# BMS.net
KiCad netlist of a schematic drawn in Altium Designer
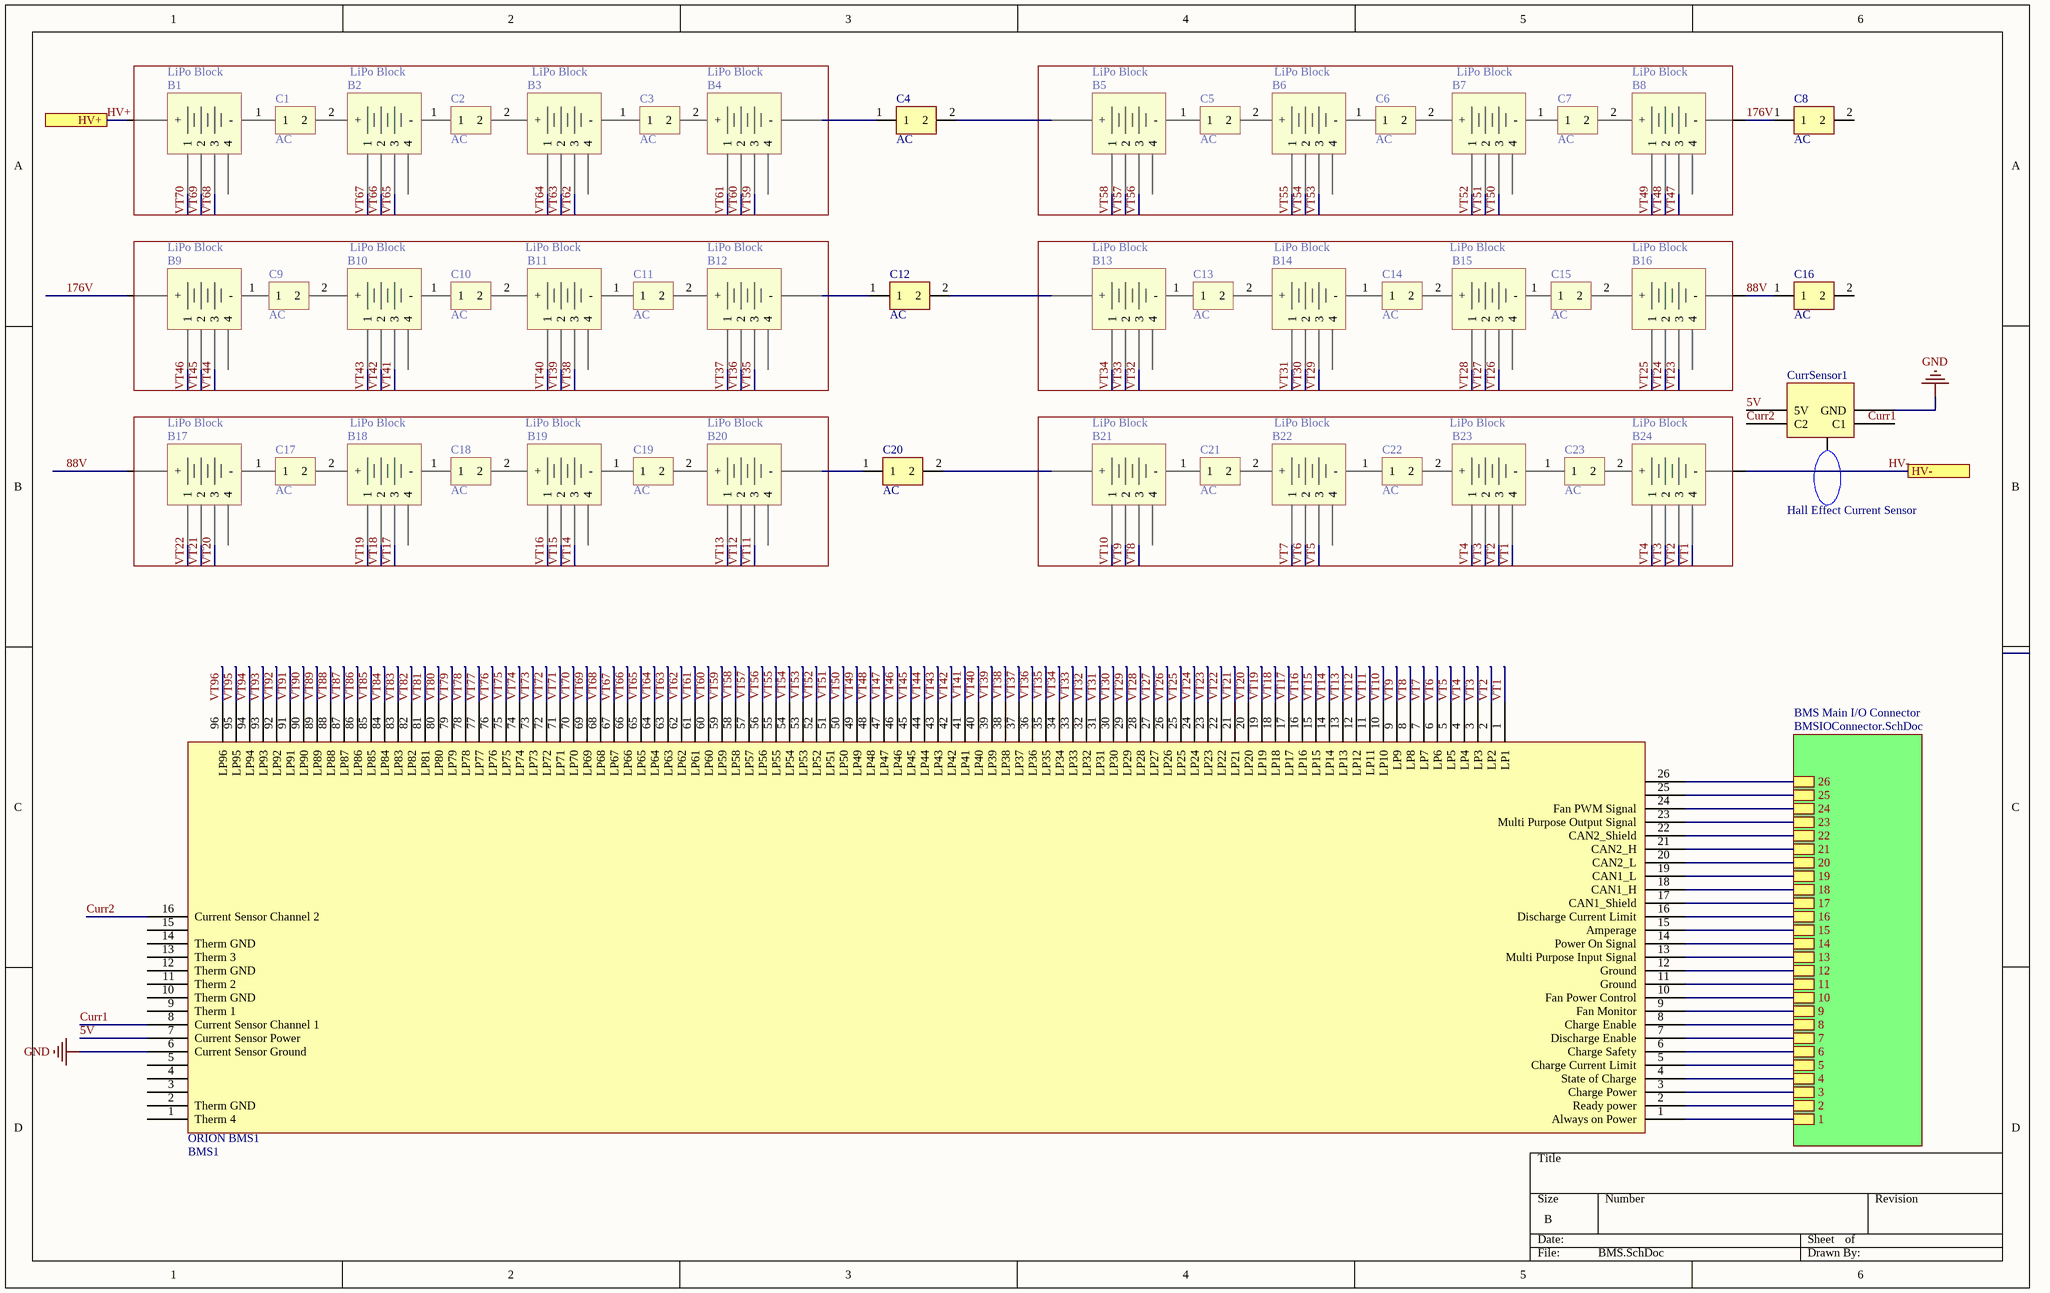
[diagram p0: BMS.SchDoc]

(export (version "E")
  (design (tool "Eeschema 10.0.6"))
  (components
    (comp (ref "B1") (value "LiPo Block") (libsource (lib "Pod3") (part "Li-Ion Cell")))
    (comp (ref "B2") (value "LiPo Block") (libsource (lib "Pod3") (part "Li-Ion Cell")))
    (comp (ref "B3") (value "LiPo Block") (libsource (lib "Pod3") (part "Li-Ion Cell")))
    (comp (ref "B4") (value "LiPo Block") (libsource (lib "Pod3") (part "Li-Ion Cell")))
    (comp (ref "B5") (value "LiPo Block") (libsource (lib "Pod3") (part "Li-Ion Cell")))
    (comp (ref "B6") (value "LiPo Block") (libsource (lib "Pod3") (part "Li-Ion Cell")))
    (comp (ref "B7") (value "LiPo Block") (libsource (lib "Pod3") (part "Li-Ion Cell")))
    (comp (ref "B8") (value "LiPo Block") (libsource (lib "Pod3") (part "Li-Ion Cell")))
    (comp (ref "B9") (value "LiPo Block") (libsource (lib "Pod3") (part "Li-Ion Cell")))
    (comp (ref "B10") (value "LiPo Block") (libsource (lib "Pod3") (part "Li-Ion Cell")))
    (comp (ref "B11") (value "LiPo Block") (libsource (lib "Pod3") (part "Li-Ion Cell")))
    (comp (ref "B12") (value "LiPo Block") (libsource (lib "Pod3") (part "Li-Ion Cell")))
    (comp (ref "B13") (value "LiPo Block") (libsource (lib "Pod3") (part "Li-Ion Cell")))
    (comp (ref "B14") (value "LiPo Block") (libsource (lib "Pod3") (part "Li-Ion Cell")))
    (comp (ref "B15") (value "LiPo Block") (libsource (lib "Pod3") (part "Li-Ion Cell")))
    (comp (ref "B16") (value "LiPo Block") (libsource (lib "Pod3") (part "Li-Ion Cell")))
    (comp (ref "B17") (value "LiPo Block") (libsource (lib "Pod3") (part "Li-Ion Cell")))
    (comp (ref "B18") (value "LiPo Block") (libsource (lib "Pod3") (part "Li-Ion Cell")))
    (comp (ref "B19") (value "LiPo Block") (libsource (lib "Pod3") (part "Li-Ion Cell")))
    (comp (ref "B20") (value "LiPo Block") (libsource (lib "Pod3") (part "Li-Ion Cell")))
    (comp (ref "B21") (value "LiPo Block") (libsource (lib "Pod3") (part "Li-Ion Cell")))
    (comp (ref "B22") (value "LiPo Block") (libsource (lib "Pod3") (part "Li-Ion Cell")))
    (comp (ref "B23") (value "LiPo Block") (libsource (lib "Pod3") (part "Li-Ion Cell")))
    (comp (ref "B24") (value "LiPo Block") (libsource (lib "Pod3") (part "Li-Ion Cell")))
    (comp (ref "C1") (value "AC") (libsource (lib "Pod3") (part "Anderson Connector")))
    (comp (ref "C2") (value "AC") (libsource (lib "Pod3") (part "Anderson Connector")))
    (comp (ref "C3") (value "AC") (libsource (lib "Pod3") (part "Anderson Connector")))
    (comp (ref "C4") (value "AC") (libsource (lib "Pod3") (part "Anderson Connector")))
    (comp (ref "C5") (value "AC") (libsource (lib "Pod3") (part "Anderson Connector")))
    (comp (ref "C6") (value "AC") (libsource (lib "Pod3") (part "Anderson Connector")))
    (comp (ref "C7") (value "AC") (libsource (lib "Pod3") (part "Anderson Connector")))
    (comp (ref "C8") (value "AC") (libsource (lib "Pod3") (part "Anderson Connector")))
    (comp (ref "C9") (value "AC") (libsource (lib "Pod3") (part "Anderson Connector")))
    (comp (ref "C10") (value "AC") (libsource (lib "Pod3") (part "Anderson Connector")))
    (comp (ref "C11") (value "AC") (libsource (lib "Pod3") (part "Anderson Connector")))
    (comp (ref "C12") (value "AC") (libsource (lib "Pod3") (part "Anderson Connector")))
    (comp (ref "C13") (value "AC") (libsource (lib "Pod3") (part "Anderson Connector")))
    (comp (ref "C14") (value "AC") (libsource (lib "Pod3") (part "Anderson Connector")))
    (comp (ref "C15") (value "AC") (libsource (lib "Pod3") (part "Anderson Connector")))
    (comp (ref "C16") (value "AC") (libsource (lib "Pod3") (part "Anderson Connector")))
    (comp (ref "C17") (value "AC") (libsource (lib "Pod3") (part "Anderson Connector")))
    (comp (ref "C18") (value "AC") (libsource (lib "Pod3") (part "Anderson Connector")))
    (comp (ref "C19") (value "AC") (libsource (lib "Pod3") (part "Anderson Connector")))
    (comp (ref "C20") (value "AC") (libsource (lib "Pod3") (part "Anderson Connector")))
    (comp (ref "C21") (value "AC") (libsource (lib "Pod3") (part "Anderson Connector")))
    (comp (ref "C22") (value "AC") (libsource (lib "Pod3") (part "Anderson Connector")))
    (comp (ref "C23") (value "AC") (libsource (lib "Pod3") (part "Anderson Connector")))
    (comp (ref "CurrSensor1")
      (value "Hall Effect Current Sensor")
      (libsource (lib "Pod3") (part "Hall Effect Current Sensor"))
    )
    (comp (ref "ORION BMS1") (value "BMS1") (libsource (lib "Pod3") (part "ORION BMS")))
  )
  (nets
    (net (code "1") (name "/1") (class "Default")
      (node (ref "ORION BMS1") (pin "1") (pinfunction "Always_on_Power_1") (pintype "passive"))
    )
    (net (code "2") (name "/2") (class "Default")
      (node (ref "ORION BMS1") (pin "2") (pinfunction "Ready_power_2") (pintype "passive"))
    )
    (net (code "3") (name "/3") (class "Default")
      (node (ref "ORION BMS1") (pin "3") (pinfunction "Charge_Power_3") (pintype "passive"))
    )
    (net (code "4") (name "/4") (class "Default")
      (node (ref "ORION BMS1") (pin "4") (pinfunction "State_of_Charge_4") (pintype "passive"))
    )
    (net (code "5") (name "/5") (class "Default")
      (node (ref "ORION BMS1") (pin "5") (pinfunction "Charge_Current_Limit_5") (pintype "passive"))
    )
    (net (code "6") (name "/5V") (class "Default")
      (node (ref "CurrSensor1") (pin "3") (pinfunction "5V_3") (pintype "passive"))
      (node (ref "ORION BMS1") (pin "7") (pinfunction "Current_Sensor_Power_7") (pintype "passive"))
    )
    (net (code "7") (name "/6") (class "Default")
      (node (ref "ORION BMS1") (pin "6") (pinfunction "Charge_Safety_6") (pintype "passive"))
    )
    (net (code "8") (name "/7") (class "Default")
      (node (ref "ORION BMS1") (pin "7") (pinfunction "Discharge_Enable_7") (pintype "passive"))
    )
    (net (code "9") (name "/8") (class "Default")
      (node (ref "ORION BMS1") (pin "8") (pinfunction "Charge_Enable_8") (pintype "passive"))
    )
    (net (code "10") (name "/9") (class "Default")
      (node (ref "ORION BMS1") (pin "9") (pinfunction "Fan_Monitor_9") (pintype "passive"))
    )
    (net (code "11") (name "/10") (class "Default")
      (node (ref "ORION BMS1") (pin "10") (pinfunction "Fan_Power_Control_10") (pintype "passive"))
    )
    (net (code "12") (name "/11") (class "Default")
      (node (ref "ORION BMS1") (pin "11") (pinfunction "Ground_11") (pintype "passive"))
    )
    (net (code "13") (name "/12") (class "Default")
      (node (ref "ORION BMS1") (pin "12") (pinfunction "Ground_12") (pintype "passive"))
    )
    (net (code "14") (name "/13") (class "Default")
      (node (ref "ORION BMS1") (pin "13") (pinfunction "Multi_Purpose_Input_Signal_13") (pintype "passive"))
    )
    (net (code "15") (name "/14") (class "Default")
      (node (ref "ORION BMS1") (pin "14") (pinfunction "Power_On_Signal_14") (pintype "passive"))
    )
    (net (code "16") (name "/15") (class "Default")
      (node (ref "ORION BMS1") (pin "15") (pinfunction "Amperage_15") (pintype "passive"))
    )
    (net (code "17") (name "/16") (class "Default")
      (node (ref "ORION BMS1") (pin "16") (pinfunction "Discharge_Current_Limit_16") (pintype "passive"))
    )
    (net (code "18") (name "/17") (class "Default")
      (node (ref "ORION BMS1") (pin "17") (pinfunction "CAN1_Shield_17") (pintype "passive"))
    )
    (net (code "19") (name "/18") (class "Default")
      (node (ref "ORION BMS1") (pin "18") (pinfunction "CAN1_H_18") (pintype "passive"))
    )
    (net (code "20") (name "/19") (class "Default")
      (node (ref "ORION BMS1") (pin "19") (pinfunction "CAN1_L_19") (pintype "passive"))
    )
    (net (code "21") (name "/20") (class "Default")
      (node (ref "ORION BMS1") (pin "20") (pinfunction "CAN2_L_20") (pintype "passive"))
    )
    (net (code "22") (name "/21") (class "Default")
      (node (ref "ORION BMS1") (pin "21") (pinfunction "CAN2_H_21") (pintype "passive"))
    )
    (net (code "23") (name "/22") (class "Default")
      (node (ref "ORION BMS1") (pin "22") (pinfunction "CAN2_Shield_22") (pintype "passive"))
    )
    (net (code "24") (name "/23") (class "Default")
      (node (ref "ORION BMS1") (pin "23") (pinfunction "Multi_Purpose_Output_Signal_23") (pintype "passive"))
    )
    (net (code "25") (name "/24") (class "Default")
      (node (ref "ORION BMS1") (pin "24") (pinfunction "Fan_PWM_Signal_24") (pintype "passive"))
    )
    (net (code "26") (name "/25") (class "Default") (node (ref "ORION BMS1") (pin "25") (pintype "passive")))
    (net (code "27") (name "/26") (class "Default") (node (ref "ORION BMS1") (pin "26") (pintype "passive")))
    (net (code "28") (name "/88V") (class "Default")
      (node (ref "B16") (pin "6") (pinfunction "-_6") (pintype "passive"))
      (node (ref "B17") (pin "5") (pinfunction "+_5") (pintype "passive"))
      (node (ref "C16") (pin "1") (pinfunction "1_1") (pintype "passive"))
    )
    (net (code "29") (name "/176V") (class "Default")
      (node (ref "B8") (pin "6") (pinfunction "-_6") (pintype "passive"))
      (node (ref "B9") (pin "5") (pinfunction "+_5") (pintype "passive"))
      (node (ref "C8") (pin "1") (pinfunction "1_1") (pintype "passive"))
    )
    (net (code "31") (name "/Curr1") (class "Default")
      (node (ref "ORION BMS1") (pin "8") (pinfunction "Current_Sensor_Channel_1_8") (pintype "passive"))
    )
    (net (code "32") (name "/Curr2") (class "Default")
      (node (ref "CurrSensor1") (pin "4") (pinfunction "C2_4") (pintype "passive"))
      (node (ref "ORION BMS1") (pin "16") (pinfunction "Current_Sensor_Channel_2_16") (pintype "passive"))
    )
    (net (code "33") (name "/HV+") (class "Default")
      (node (ref "B1") (pin "5") (pinfunction "+_5") (pintype "passive"))
    )
    (net (code "34") (name "/HV-") (class "Default")
      (node (ref "B24") (pin "6") (pinfunction "-_6") (pintype "passive"))
    )
    (net (code "35") (name "/VT1") (class "Default")
      (node (ref "B23") (pin "4") (pinfunction "4_4") (pintype "passive"))
      (node (ref "B24") (pin "4") (pinfunction "4_4") (pintype "passive"))
      (node (ref "ORION BMS1") (pin "1") (pinfunction "LP1_1") (pintype "passive"))
    )
    (net (code "36") (name "/VT2") (class "Default")
      (node (ref "B23") (pin "3") (pinfunction "3_3") (pintype "passive"))
      (node (ref "B24") (pin "3") (pinfunction "3_3") (pintype "passive"))
      (node (ref "ORION BMS1") (pin "2") (pinfunction "LP2_2") (pintype "passive"))
    )
    (net (code "37") (name "/VT3") (class "Default")
      (node (ref "B23") (pin "2") (pinfunction "2_2") (pintype "passive"))
      (node (ref "B24") (pin "2") (pinfunction "2_2") (pintype "passive"))
      (node (ref "ORION BMS1") (pin "3") (pinfunction "LP3_3") (pintype "passive"))
    )
    (net (code "38") (name "/VT4") (class "Default")
      (node (ref "B23") (pin "1") (pinfunction "1_1") (pintype "passive"))
      (node (ref "B24") (pin "1") (pinfunction "1_1") (pintype "passive"))
      (node (ref "ORION BMS1") (pin "4") (pinfunction "LP4_4") (pintype "passive"))
    )
    (net (code "39") (name "/VT5") (class "Default")
      (node (ref "B22") (pin "3") (pinfunction "3_3") (pintype "passive"))
      (node (ref "ORION BMS1") (pin "5") (pinfunction "LP5_5") (pintype "passive"))
    )
    (net (code "40") (name "/VT6") (class "Default")
      (node (ref "B22") (pin "2") (pinfunction "2_2") (pintype "passive"))
      (node (ref "ORION BMS1") (pin "6") (pinfunction "LP6_6") (pintype "passive"))
    )
    (net (code "41") (name "/VT7") (class "Default")
      (node (ref "B22") (pin "1") (pinfunction "1_1") (pintype "passive"))
      (node (ref "ORION BMS1") (pin "7") (pinfunction "LP7_7") (pintype "passive"))
    )
    (net (code "42") (name "/VT8") (class "Default")
      (node (ref "B21") (pin "3") (pinfunction "3_3") (pintype "passive"))
      (node (ref "ORION BMS1") (pin "8") (pinfunction "LP8_8") (pintype "passive"))
    )
    (net (code "43") (name "/VT9") (class "Default")
      (node (ref "B21") (pin "2") (pinfunction "2_2") (pintype "passive"))
      (node (ref "ORION BMS1") (pin "9") (pinfunction "LP9_9") (pintype "passive"))
    )
    (net (code "44") (name "/VT10") (class "Default")
      (node (ref "B21") (pin "1") (pinfunction "1_1") (pintype "passive"))
      (node (ref "ORION BMS1") (pin "10") (pinfunction "LP10_10") (pintype "passive"))
    )
    (net (code "45") (name "/VT11") (class "Default")
      (node (ref "B20") (pin "3") (pinfunction "3_3") (pintype "passive"))
      (node (ref "ORION BMS1") (pin "11") (pinfunction "LP11_11") (pintype "passive"))
    )
    (net (code "46") (name "/VT12") (class "Default")
      (node (ref "B20") (pin "2") (pinfunction "2_2") (pintype "passive"))
      (node (ref "ORION BMS1") (pin "12") (pinfunction "LP12_12") (pintype "passive"))
    )
    (net (code "47") (name "/VT13") (class "Default")
      (node (ref "B20") (pin "1") (pinfunction "1_1") (pintype "passive"))
      (node (ref "ORION BMS1") (pin "13") (pinfunction "LP13_13") (pintype "passive"))
    )
    (net (code "48") (name "/VT14") (class "Default")
      (node (ref "B19") (pin "3") (pinfunction "3_3") (pintype "passive"))
      (node (ref "ORION BMS1") (pin "14") (pinfunction "LP14_14") (pintype "passive"))
    )
    (net (code "49") (name "/VT15") (class "Default")
      (node (ref "B19") (pin "2") (pinfunction "2_2") (pintype "passive"))
      (node (ref "ORION BMS1") (pin "15") (pinfunction "LP15_15") (pintype "passive"))
    )
    (net (code "50") (name "/VT16") (class "Default")
      (node (ref "B19") (pin "1") (pinfunction "1_1") (pintype "passive"))
      (node (ref "ORION BMS1") (pin "16") (pinfunction "LP16_16") (pintype "passive"))
    )
    (net (code "51") (name "/VT17") (class "Default")
      (node (ref "B18") (pin "3") (pinfunction "3_3") (pintype "passive"))
      (node (ref "ORION BMS1") (pin "17") (pinfunction "LP17_17") (pintype "passive"))
    )
    (net (code "52") (name "/VT18") (class "Default")
      (node (ref "B18") (pin "2") (pinfunction "2_2") (pintype "passive"))
      (node (ref "ORION BMS1") (pin "18") (pinfunction "LP18_18") (pintype "passive"))
    )
    (net (code "53") (name "/VT19") (class "Default")
      (node (ref "B18") (pin "1") (pinfunction "1_1") (pintype "passive"))
      (node (ref "ORION BMS1") (pin "19") (pinfunction "LP19_19") (pintype "passive"))
    )
    (net (code "54") (name "/VT20") (class "Default")
      (node (ref "B17") (pin "3") (pinfunction "3_3") (pintype "passive"))
      (node (ref "ORION BMS1") (pin "20") (pinfunction "LP20_20") (pintype "passive"))
    )
    (net (code "55") (name "/VT21") (class "Default")
      (node (ref "B17") (pin "2") (pinfunction "2_2") (pintype "passive"))
      (node (ref "ORION BMS1") (pin "21") (pinfunction "LP21_21") (pintype "passive"))
    )
    (net (code "56") (name "/VT22") (class "Default")
      (node (ref "B17") (pin "1") (pinfunction "1_1") (pintype "passive"))
      (node (ref "ORION BMS1") (pin "22") (pinfunction "LP22_22") (pintype "passive"))
    )
    (net (code "57") (name "/VT23") (class "Default")
      (node (ref "B16") (pin "3") (pinfunction "3_3") (pintype "passive"))
      (node (ref "ORION BMS1") (pin "23") (pinfunction "LP23_23") (pintype "passive"))
    )
    (net (code "58") (name "/VT24") (class "Default")
      (node (ref "B16") (pin "2") (pinfunction "2_2") (pintype "passive"))
      (node (ref "ORION BMS1") (pin "24") (pinfunction "LP24_24") (pintype "passive"))
    )
    (net (code "59") (name "/VT25") (class "Default")
      (node (ref "B16") (pin "1") (pinfunction "1_1") (pintype "passive"))
      (node (ref "ORION BMS1") (pin "25") (pinfunction "LP25_25") (pintype "passive"))
    )
    (net (code "60") (name "/VT26") (class "Default")
      (node (ref "B15") (pin "3") (pinfunction "3_3") (pintype "passive"))
      (node (ref "ORION BMS1") (pin "26") (pinfunction "LP26_26") (pintype "passive"))
    )
    (net (code "61") (name "/VT27") (class "Default")
      (node (ref "B15") (pin "2") (pinfunction "2_2") (pintype "passive"))
      (node (ref "ORION BMS1") (pin "27") (pinfunction "LP27_27") (pintype "passive"))
    )
    (net (code "62") (name "/VT28") (class "Default")
      (node (ref "B15") (pin "1") (pinfunction "1_1") (pintype "passive"))
      (node (ref "ORION BMS1") (pin "28") (pinfunction "LP28_28") (pintype "passive"))
    )
    (net (code "63") (name "/VT29") (class "Default")
      (node (ref "B14") (pin "3") (pinfunction "3_3") (pintype "passive"))
      (node (ref "ORION BMS1") (pin "29") (pinfunction "LP29_29") (pintype "passive"))
    )
    (net (code "64") (name "/VT30") (class "Default")
      (node (ref "B14") (pin "2") (pinfunction "2_2") (pintype "passive"))
      (node (ref "ORION BMS1") (pin "30") (pinfunction "LP30_30") (pintype "passive"))
    )
    (net (code "65") (name "/VT31") (class "Default")
      (node (ref "B14") (pin "1") (pinfunction "1_1") (pintype "passive"))
      (node (ref "ORION BMS1") (pin "31") (pinfunction "LP31_31") (pintype "passive"))
    )
    (net (code "66") (name "/VT32") (class "Default")
      (node (ref "B13") (pin "3") (pinfunction "3_3") (pintype "passive"))
      (node (ref "ORION BMS1") (pin "32") (pinfunction "LP32_32") (pintype "passive"))
    )
    (net (code "67") (name "/VT33") (class "Default")
      (node (ref "B13") (pin "2") (pinfunction "2_2") (pintype "passive"))
      (node (ref "ORION BMS1") (pin "33") (pinfunction "LP33_33") (pintype "passive"))
    )
    (net (code "68") (name "/VT34") (class "Default")
      (node (ref "B13") (pin "1") (pinfunction "1_1") (pintype "passive"))
      (node (ref "ORION BMS1") (pin "34") (pinfunction "LP34_34") (pintype "passive"))
    )
    (net (code "69") (name "/VT35") (class "Default")
      (node (ref "B12") (pin "3") (pinfunction "3_3") (pintype "passive"))
      (node (ref "ORION BMS1") (pin "35") (pinfunction "LP35_35") (pintype "passive"))
    )
    (net (code "70") (name "/VT36") (class "Default")
      (node (ref "B12") (pin "2") (pinfunction "2_2") (pintype "passive"))
      (node (ref "ORION BMS1") (pin "36") (pinfunction "LP36_36") (pintype "passive"))
    )
    (net (code "71") (name "/VT37") (class "Default")
      (node (ref "B12") (pin "1") (pinfunction "1_1") (pintype "passive"))
      (node (ref "ORION BMS1") (pin "37") (pinfunction "LP37_37") (pintype "passive"))
    )
    (net (code "72") (name "/VT38") (class "Default")
      (node (ref "B11") (pin "3") (pinfunction "3_3") (pintype "passive"))
      (node (ref "ORION BMS1") (pin "38") (pinfunction "LP38_38") (pintype "passive"))
    )
    (net (code "73") (name "/VT39") (class "Default")
      (node (ref "B11") (pin "2") (pinfunction "2_2") (pintype "passive"))
      (node (ref "ORION BMS1") (pin "39") (pinfunction "LP39_39") (pintype "passive"))
    )
    (net (code "74") (name "/VT40") (class "Default")
      (node (ref "B11") (pin "1") (pinfunction "1_1") (pintype "passive"))
      (node (ref "ORION BMS1") (pin "40") (pinfunction "LP40_40") (pintype "passive"))
    )
    (net (code "75") (name "/VT41") (class "Default")
      (node (ref "B10") (pin "3") (pinfunction "3_3") (pintype "passive"))
      (node (ref "ORION BMS1") (pin "41") (pinfunction "LP41_41") (pintype "passive"))
    )
    (net (code "76") (name "/VT42") (class "Default")
      (node (ref "B10") (pin "2") (pinfunction "2_2") (pintype "passive"))
      (node (ref "ORION BMS1") (pin "42") (pinfunction "LP42_42") (pintype "passive"))
    )
    (net (code "77") (name "/VT43") (class "Default")
      (node (ref "B10") (pin "1") (pinfunction "1_1") (pintype "passive"))
      (node (ref "ORION BMS1") (pin "43") (pinfunction "LP43_43") (pintype "passive"))
    )
    (net (code "78") (name "/VT44") (class "Default")
      (node (ref "B9") (pin "3") (pinfunction "3_3") (pintype "passive"))
      (node (ref "ORION BMS1") (pin "44") (pinfunction "LP44_44") (pintype "passive"))
    )
    (net (code "79") (name "/VT45") (class "Default")
      (node (ref "B9") (pin "2") (pinfunction "2_2") (pintype "passive"))
      (node (ref "ORION BMS1") (pin "45") (pinfunction "LP45_45") (pintype "passive"))
    )
    (net (code "80") (name "/VT46") (class "Default")
      (node (ref "B9") (pin "1") (pinfunction "1_1") (pintype "passive"))
      (node (ref "ORION BMS1") (pin "46") (pinfunction "LP46_46") (pintype "passive"))
    )
    (net (code "81") (name "/VT47") (class "Default")
      (node (ref "B8") (pin "3") (pinfunction "3_3") (pintype "passive"))
      (node (ref "ORION BMS1") (pin "47") (pinfunction "LP47_47") (pintype "passive"))
    )
    (net (code "82") (name "/VT48") (class "Default")
      (node (ref "B8") (pin "2") (pinfunction "2_2") (pintype "passive"))
      (node (ref "ORION BMS1") (pin "48") (pinfunction "LP48_48") (pintype "passive"))
    )
    (net (code "83") (name "/VT49") (class "Default")
      (node (ref "B8") (pin "1") (pinfunction "1_1") (pintype "passive"))
      (node (ref "ORION BMS1") (pin "49") (pinfunction "LP49_49") (pintype "passive"))
    )
    (net (code "84") (name "/VT50") (class "Default")
      (node (ref "B7") (pin "3") (pinfunction "3_3") (pintype "passive"))
      (node (ref "ORION BMS1") (pin "50") (pinfunction "LP50_50") (pintype "passive"))
    )
    (net (code "85") (name "/VT51") (class "Default")
      (node (ref "B7") (pin "2") (pinfunction "2_2") (pintype "passive"))
      (node (ref "ORION BMS1") (pin "51") (pinfunction "LP51_51") (pintype "passive"))
    )
    (net (code "86") (name "/VT52") (class "Default")
      (node (ref "B7") (pin "1") (pinfunction "1_1") (pintype "passive"))
      (node (ref "ORION BMS1") (pin "52") (pinfunction "LP52_52") (pintype "passive"))
    )
    (net (code "87") (name "/VT53") (class "Default")
      (node (ref "B6") (pin "3") (pinfunction "3_3") (pintype "passive"))
      (node (ref "ORION BMS1") (pin "53") (pinfunction "LP53_53") (pintype "passive"))
    )
    (net (code "88") (name "/VT54") (class "Default")
      (node (ref "B6") (pin "2") (pinfunction "2_2") (pintype "passive"))
      (node (ref "ORION BMS1") (pin "54") (pinfunction "LP54_54") (pintype "passive"))
    )
    (net (code "89") (name "/VT55") (class "Default")
      (node (ref "B6") (pin "1") (pinfunction "1_1") (pintype "passive"))
      (node (ref "ORION BMS1") (pin "55") (pinfunction "LP55_55") (pintype "passive"))
    )
    (net (code "90") (name "/VT56") (class "Default")
      (node (ref "B5") (pin "3") (pinfunction "3_3") (pintype "passive"))
      (node (ref "ORION BMS1") (pin "56") (pinfunction "LP56_56") (pintype "passive"))
    )
    (net (code "91") (name "/VT57") (class "Default")
      (node (ref "B5") (pin "2") (pinfunction "2_2") (pintype "passive"))
      (node (ref "ORION BMS1") (pin "57") (pinfunction "LP57_57") (pintype "passive"))
    )
    (net (code "92") (name "/VT58") (class "Default")
      (node (ref "B5") (pin "1") (pinfunction "1_1") (pintype "passive"))
      (node (ref "ORION BMS1") (pin "58") (pinfunction "LP58_58") (pintype "passive"))
    )
    (net (code "93") (name "/VT59") (class "Default")
      (node (ref "B4") (pin "3") (pinfunction "3_3") (pintype "passive"))
      (node (ref "ORION BMS1") (pin "59") (pinfunction "LP59_59") (pintype "passive"))
    )
    (net (code "94") (name "/VT60") (class "Default")
      (node (ref "B4") (pin "2") (pinfunction "2_2") (pintype "passive"))
      (node (ref "ORION BMS1") (pin "60") (pinfunction "LP60_60") (pintype "passive"))
    )
    (net (code "95") (name "/VT61") (class "Default")
      (node (ref "B4") (pin "1") (pinfunction "1_1") (pintype "passive"))
      (node (ref "ORION BMS1") (pin "61") (pinfunction "LP61_61") (pintype "passive"))
    )
    (net (code "96") (name "/VT62") (class "Default")
      (node (ref "B3") (pin "3") (pinfunction "3_3") (pintype "passive"))
      (node (ref "ORION BMS1") (pin "62") (pinfunction "LP62_62") (pintype "passive"))
    )
    (net (code "97") (name "/VT63") (class "Default")
      (node (ref "B3") (pin "2") (pinfunction "2_2") (pintype "passive"))
      (node (ref "ORION BMS1") (pin "63") (pinfunction "LP63_63") (pintype "passive"))
    )
    (net (code "98") (name "/VT64") (class "Default")
      (node (ref "B3") (pin "1") (pinfunction "1_1") (pintype "passive"))
      (node (ref "ORION BMS1") (pin "64") (pinfunction "LP64_64") (pintype "passive"))
    )
    (net (code "99") (name "/VT65") (class "Default")
      (node (ref "B2") (pin "3") (pinfunction "3_3") (pintype "passive"))
      (node (ref "ORION BMS1") (pin "65") (pinfunction "LP65_65") (pintype "passive"))
    )
    (net (code "100") (name "/VT66") (class "Default")
      (node (ref "B2") (pin "2") (pinfunction "2_2") (pintype "passive"))
      (node (ref "ORION BMS1") (pin "66") (pinfunction "LP66_66") (pintype "passive"))
    )
    (net (code "101") (name "/VT67") (class "Default")
      (node (ref "B2") (pin "1") (pinfunction "1_1") (pintype "passive"))
      (node (ref "ORION BMS1") (pin "67") (pinfunction "LP67_67") (pintype "passive"))
    )
    (net (code "102") (name "/VT68") (class "Default")
      (node (ref "B1") (pin "3") (pinfunction "3_3") (pintype "passive"))
      (node (ref "ORION BMS1") (pin "68") (pinfunction "LP68_68") (pintype "passive"))
    )
    (net (code "103") (name "/VT69") (class "Default")
      (node (ref "B1") (pin "2") (pinfunction "2_2") (pintype "passive"))
      (node (ref "ORION BMS1") (pin "69") (pinfunction "LP69_69") (pintype "passive"))
    )
    (net (code "104") (name "/VT70") (class "Default")
      (node (ref "B1") (pin "1") (pinfunction "1_1") (pintype "passive"))
      (node (ref "ORION BMS1") (pin "70") (pinfunction "LP70_70") (pintype "passive"))
    )
    (net (code "105") (name "/VT71") (class "Default")
      (node (ref "ORION BMS1") (pin "71") (pinfunction "LP71_71") (pintype "passive"))
    )
    (net (code "106") (name "/VT72") (class "Default")
      (node (ref "ORION BMS1") (pin "72") (pinfunction "LP72_72") (pintype "passive"))
    )
    (net (code "107") (name "/VT73") (class "Default")
      (node (ref "ORION BMS1") (pin "73") (pinfunction "LP73_73") (pintype "passive"))
    )
    (net (code "108") (name "/VT74") (class "Default")
      (node (ref "ORION BMS1") (pin "74") (pinfunction "LP74_74") (pintype "passive"))
    )
    (net (code "109") (name "/VT75") (class "Default")
      (node (ref "ORION BMS1") (pin "75") (pinfunction "LP75_75") (pintype "passive"))
    )
    (net (code "110") (name "/VT76") (class "Default")
      (node (ref "ORION BMS1") (pin "76") (pinfunction "LP76_76") (pintype "passive"))
    )
    (net (code "111") (name "/VT77") (class "Default")
      (node (ref "ORION BMS1") (pin "77") (pinfunction "LP77_77") (pintype "passive"))
    )
    (net (code "112") (name "/VT78") (class "Default")
      (node (ref "ORION BMS1") (pin "78") (pinfunction "LP78_78") (pintype "passive"))
    )
    (net (code "113") (name "/VT79") (class "Default")
      (node (ref "ORION BMS1") (pin "79") (pinfunction "LP79_79") (pintype "passive"))
    )
    (net (code "114") (name "/VT80") (class "Default")
      (node (ref "ORION BMS1") (pin "80") (pinfunction "LP80_80") (pintype "passive"))
    )
    (net (code "115") (name "/VT81") (class "Default")
      (node (ref "ORION BMS1") (pin "81") (pinfunction "LP81_81") (pintype "passive"))
    )
    (net (code "116") (name "/VT82") (class "Default")
      (node (ref "ORION BMS1") (pin "82") (pinfunction "LP82_82") (pintype "passive"))
    )
    (net (code "117") (name "/VT83") (class "Default")
      (node (ref "ORION BMS1") (pin "83") (pinfunction "LP83_83") (pintype "passive"))
    )
    (net (code "118") (name "/VT84") (class "Default")
      (node (ref "ORION BMS1") (pin "84") (pinfunction "LP84_84") (pintype "passive"))
    )
    (net (code "119") (name "/VT85") (class "Default")
      (node (ref "ORION BMS1") (pin "85") (pinfunction "LP85_85") (pintype "passive"))
    )
    (net (code "120") (name "/VT86") (class "Default")
      (node (ref "ORION BMS1") (pin "86") (pinfunction "LP86_86") (pintype "passive"))
    )
    (net (code "121") (name "/VT87") (class "Default")
      (node (ref "ORION BMS1") (pin "87") (pinfunction "LP87_87") (pintype "passive"))
    )
    (net (code "122") (name "/VT88") (class "Default")
      (node (ref "ORION BMS1") (pin "88") (pinfunction "LP88_88") (pintype "passive"))
    )
    (net (code "123") (name "/VT89") (class "Default")
      (node (ref "ORION BMS1") (pin "89") (pinfunction "LP89_89") (pintype "passive"))
    )
    (net (code "124") (name "/VT90") (class "Default")
      (node (ref "ORION BMS1") (pin "90") (pinfunction "LP90_90") (pintype "passive"))
    )
    (net (code "125") (name "/VT91") (class "Default")
      (node (ref "ORION BMS1") (pin "91") (pinfunction "LP91_91") (pintype "passive"))
    )
    (net (code "126") (name "/VT92") (class "Default")
      (node (ref "ORION BMS1") (pin "92") (pinfunction "LP92_92") (pintype "passive"))
    )
    (net (code "127") (name "/VT93") (class "Default")
      (node (ref "ORION BMS1") (pin "93") (pinfunction "LP93_93") (pintype "passive"))
    )
    (net (code "128") (name "/VT94") (class "Default")
      (node (ref "ORION BMS1") (pin "94") (pinfunction "LP94_94") (pintype "passive"))
    )
    (net (code "129") (name "/VT95") (class "Default")
      (node (ref "ORION BMS1") (pin "95") (pinfunction "LP95_95") (pintype "passive"))
    )
    (net (code "130") (name "/VT96") (class "Default")
      (node (ref "ORION BMS1") (pin "96") (pinfunction "LP96_96") (pintype "passive"))
    )
    (net (code "131") (name "GND") (class "Default")
      (node (ref "CurrSensor1") (pin "2") (pinfunction "GND_2") (pintype "passive"))
      (node (ref "ORION BMS1") (pin "6") (pinfunction "Current_Sensor_Ground_6") (pintype "passive"))
    )
    (net (code "132") (name "Net-(B4--)") (class "Default")
      (node (ref "B4") (pin "6") (pinfunction "-_6") (pintype "passive"))
      (node (ref "C4") (pin "1") (pinfunction "1_1") (pintype "passive"))
    )
    (net (code "133") (name "Net-(B5-+)") (class "Default")
      (node (ref "B5") (pin "5") (pinfunction "+_5") (pintype "passive"))
      (node (ref "C4") (pin "2") (pinfunction "2_2") (pintype "passive"))
    )
    (net (code "134") (name "Net-(B12--)") (class "Default")
      (node (ref "B12") (pin "6") (pinfunction "-_6") (pintype "passive"))
      (node (ref "C12") (pin "1") (pinfunction "1_1") (pintype "passive"))
    )
    (net (code "135") (name "Net-(B13-+)") (class "Default")
      (node (ref "B13") (pin "5") (pinfunction "+_5") (pintype "passive"))
      (node (ref "C12") (pin "2") (pinfunction "2_2") (pintype "passive"))
    )
    (net (code "136") (name "Net-(B20--)") (class "Default")
      (node (ref "B20") (pin "6") (pinfunction "-_6") (pintype "passive"))
      (node (ref "C20") (pin "1") (pinfunction "1_1") (pintype "passive"))
    )
    (net (code "137") (name "Net-(B21-+)") (class "Default")
      (node (ref "B21") (pin "5") (pinfunction "+_5") (pintype "passive"))
      (node (ref "C20") (pin "2") (pinfunction "2_2") (pintype "passive"))
    )
    (net (code "138") (name "unconnected-(B1---Pad6)") (class "Default")
      (node (ref "B1") (pin "6") (pinfunction "-_6") (pintype "passive"))
    )
    (net (code "139") (name "unconnected-(B1-Pad4)") (class "Default")
      (node (ref "B1") (pin "4") (pinfunction "4_4") (pintype "passive"))
    )
    (net (code "140") (name "unconnected-(B2-+-Pad5)") (class "Default")
      (node (ref "B2") (pin "5") (pinfunction "+_5") (pintype "passive"))
    )
    (net (code "141") (name "unconnected-(B2---Pad6)") (class "Default")
      (node (ref "B2") (pin "6") (pinfunction "-_6") (pintype "passive"))
    )
    (net (code "142") (name "unconnected-(B2-Pad4)") (class "Default")
      (node (ref "B2") (pin "4") (pinfunction "4_4") (pintype "passive"))
    )
    (net (code "143") (name "unconnected-(B3-+-Pad5)") (class "Default")
      (node (ref "B3") (pin "5") (pinfunction "+_5") (pintype "passive"))
    )
    (net (code "144") (name "unconnected-(B3---Pad6)") (class "Default")
      (node (ref "B3") (pin "6") (pinfunction "-_6") (pintype "passive"))
    )
    (net (code "145") (name "unconnected-(B3-Pad4)") (class "Default")
      (node (ref "B3") (pin "4") (pinfunction "4_4") (pintype "passive"))
    )
    (net (code "146") (name "unconnected-(B4-+-Pad5)") (class "Default")
      (node (ref "B4") (pin "5") (pinfunction "+_5") (pintype "passive"))
    )
    (net (code "147") (name "unconnected-(B4-Pad4)") (class "Default")
      (node (ref "B4") (pin "4") (pinfunction "4_4") (pintype "passive"))
    )
    (net (code "148") (name "unconnected-(B5---Pad6)") (class "Default")
      (node (ref "B5") (pin "6") (pinfunction "-_6") (pintype "passive"))
    )
    (net (code "149") (name "unconnected-(B5-Pad4)") (class "Default")
      (node (ref "B5") (pin "4") (pinfunction "4_4") (pintype "passive"))
    )
    (net (code "150") (name "unconnected-(B6-+-Pad5)") (class "Default")
      (node (ref "B6") (pin "5") (pinfunction "+_5") (pintype "passive"))
    )
    (net (code "151") (name "unconnected-(B6---Pad6)") (class "Default")
      (node (ref "B6") (pin "6") (pinfunction "-_6") (pintype "passive"))
    )
    (net (code "152") (name "unconnected-(B6-Pad4)") (class "Default")
      (node (ref "B6") (pin "4") (pinfunction "4_4") (pintype "passive"))
    )
    (net (code "153") (name "unconnected-(B7-+-Pad5)") (class "Default")
      (node (ref "B7") (pin "5") (pinfunction "+_5") (pintype "passive"))
    )
    (net (code "154") (name "unconnected-(B7---Pad6)") (class "Default")
      (node (ref "B7") (pin "6") (pinfunction "-_6") (pintype "passive"))
    )
    (net (code "155") (name "unconnected-(B7-Pad4)") (class "Default")
      (node (ref "B7") (pin "4") (pinfunction "4_4") (pintype "passive"))
    )
    (net (code "156") (name "unconnected-(B8-+-Pad5)") (class "Default")
      (node (ref "B8") (pin "5") (pinfunction "+_5") (pintype "passive"))
    )
    (net (code "157") (name "unconnected-(B8-Pad4)") (class "Default")
      (node (ref "B8") (pin "4") (pinfunction "4_4") (pintype "passive"))
    )
    (net (code "158") (name "unconnected-(B9---Pad6)") (class "Default")
      (node (ref "B9") (pin "6") (pinfunction "-_6") (pintype "passive"))
    )
    (net (code "159") (name "unconnected-(B9-Pad4)") (class "Default")
      (node (ref "B9") (pin "4") (pinfunction "4_4") (pintype "passive"))
    )
    (net (code "160") (name "unconnected-(B10-+-Pad5)") (class "Default")
      (node (ref "B10") (pin "5") (pinfunction "+_5") (pintype "passive"))
    )
    (net (code "161") (name "unconnected-(B10---Pad6)") (class "Default")
      (node (ref "B10") (pin "6") (pinfunction "-_6") (pintype "passive"))
    )
    (net (code "162") (name "unconnected-(B10-Pad4)") (class "Default")
      (node (ref "B10") (pin "4") (pinfunction "4_4") (pintype "passive"))
    )
    (net (code "163") (name "unconnected-(B11-+-Pad5)") (class "Default")
      (node (ref "B11") (pin "5") (pinfunction "+_5") (pintype "passive"))
    )
    (net (code "164") (name "unconnected-(B11---Pad6)") (class "Default")
      (node (ref "B11") (pin "6") (pinfunction "-_6") (pintype "passive"))
    )
    (net (code "165") (name "unconnected-(B11-Pad4)") (class "Default")
      (node (ref "B11") (pin "4") (pinfunction "4_4") (pintype "passive"))
    )
    (net (code "166") (name "unconnected-(B12-+-Pad5)") (class "Default")
      (node (ref "B12") (pin "5") (pinfunction "+_5") (pintype "passive"))
    )
    (net (code "167") (name "unconnected-(B12-Pad4)") (class "Default")
      (node (ref "B12") (pin "4") (pinfunction "4_4") (pintype "passive"))
    )
    (net (code "168") (name "unconnected-(B13---Pad6)") (class "Default")
      (node (ref "B13") (pin "6") (pinfunction "-_6") (pintype "passive"))
    )
    (net (code "169") (name "unconnected-(B13-Pad4)") (class "Default")
      (node (ref "B13") (pin "4") (pinfunction "4_4") (pintype "passive"))
    )
    (net (code "170") (name "unconnected-(B14-+-Pad5)") (class "Default")
      (node (ref "B14") (pin "5") (pinfunction "+_5") (pintype "passive"))
    )
    (net (code "171") (name "unconnected-(B14---Pad6)") (class "Default")
      (node (ref "B14") (pin "6") (pinfunction "-_6") (pintype "passive"))
    )
    (net (code "172") (name "unconnected-(B14-Pad4)") (class "Default")
      (node (ref "B14") (pin "4") (pinfunction "4_4") (pintype "passive"))
    )
    (net (code "173") (name "unconnected-(B15-+-Pad5)") (class "Default")
      (node (ref "B15") (pin "5") (pinfunction "+_5") (pintype "passive"))
    )
    (net (code "174") (name "unconnected-(B15---Pad6)") (class "Default")
      (node (ref "B15") (pin "6") (pinfunction "-_6") (pintype "passive"))
    )
    (net (code "175") (name "unconnected-(B15-Pad4)") (class "Default")
      (node (ref "B15") (pin "4") (pinfunction "4_4") (pintype "passive"))
    )
    (net (code "176") (name "unconnected-(B16-+-Pad5)") (class "Default")
      (node (ref "B16") (pin "5") (pinfunction "+_5") (pintype "passive"))
    )
    (net (code "177") (name "unconnected-(B16-Pad4)") (class "Default")
      (node (ref "B16") (pin "4") (pinfunction "4_4") (pintype "passive"))
    )
    (net (code "178") (name "unconnected-(B17---Pad6)") (class "Default")
      (node (ref "B17") (pin "6") (pinfunction "-_6") (pintype "passive"))
    )
    (net (code "179") (name "unconnected-(B17-Pad4)") (class "Default")
      (node (ref "B17") (pin "4") (pinfunction "4_4") (pintype "passive"))
    )
    (net (code "180") (name "unconnected-(B18-+-Pad5)") (class "Default")
      (node (ref "B18") (pin "5") (pinfunction "+_5") (pintype "passive"))
    )
    (net (code "181") (name "unconnected-(B18---Pad6)") (class "Default")
      (node (ref "B18") (pin "6") (pinfunction "-_6") (pintype "passive"))
    )
    (net (code "182") (name "unconnected-(B18-Pad4)") (class "Default")
      (node (ref "B18") (pin "4") (pinfunction "4_4") (pintype "passive"))
    )
    (net (code "183") (name "unconnected-(B19-+-Pad5)") (class "Default")
      (node (ref "B19") (pin "5") (pinfunction "+_5") (pintype "passive"))
    )
    (net (code "184") (name "unconnected-(B19---Pad6)") (class "Default")
      (node (ref "B19") (pin "6") (pinfunction "-_6") (pintype "passive"))
    )
    (net (code "185") (name "unconnected-(B19-Pad4)") (class "Default")
      (node (ref "B19") (pin "4") (pinfunction "4_4") (pintype "passive"))
    )
    (net (code "186") (name "unconnected-(B20-+-Pad5)") (class "Default")
      (node (ref "B20") (pin "5") (pinfunction "+_5") (pintype "passive"))
    )
    (net (code "187") (name "unconnected-(B20-Pad4)") (class "Default")
      (node (ref "B20") (pin "4") (pinfunction "4_4") (pintype "passive"))
    )
    (net (code "188") (name "unconnected-(B21---Pad6)") (class "Default")
      (node (ref "B21") (pin "6") (pinfunction "-_6") (pintype "passive"))
    )
    (net (code "189") (name "unconnected-(B21-Pad4)") (class "Default")
      (node (ref "B21") (pin "4") (pinfunction "4_4") (pintype "passive"))
    )
    (net (code "190") (name "unconnected-(B22-+-Pad5)") (class "Default")
      (node (ref "B22") (pin "5") (pinfunction "+_5") (pintype "passive"))
    )
    (net (code "191") (name "unconnected-(B22---Pad6)") (class "Default")
      (node (ref "B22") (pin "6") (pinfunction "-_6") (pintype "passive"))
    )
    (net (code "192") (name "unconnected-(B22-Pad4)") (class "Default")
      (node (ref "B22") (pin "4") (pinfunction "4_4") (pintype "passive"))
    )
    (net (code "193") (name "unconnected-(B23-+-Pad5)") (class "Default")
      (node (ref "B23") (pin "5") (pinfunction "+_5") (pintype "passive"))
    )
    (net (code "194") (name "unconnected-(B23---Pad6)") (class "Default")
      (node (ref "B23") (pin "6") (pinfunction "-_6") (pintype "passive"))
    )
    (net (code "195") (name "unconnected-(B24-+-Pad5)") (class "Default")
      (node (ref "B24") (pin "5") (pinfunction "+_5") (pintype "passive"))
    )
    (net (code "196") (name "unconnected-(C1-Pad1)") (class "Default")
      (node (ref "C1") (pin "1") (pinfunction "1_1") (pintype "passive"))
    )
    (net (code "197") (name "unconnected-(C1-Pad2)") (class "Default")
      (node (ref "C1") (pin "2") (pinfunction "2_2") (pintype "passive"))
    )
    (net (code "198") (name "unconnected-(C2-Pad1)") (class "Default")
      (node (ref "C2") (pin "1") (pinfunction "1_1") (pintype "passive"))
    )
    (net (code "199") (name "unconnected-(C2-Pad2)") (class "Default")
      (node (ref "C2") (pin "2") (pinfunction "2_2") (pintype "passive"))
    )
    (net (code "200") (name "unconnected-(C3-Pad1)") (class "Default")
      (node (ref "C3") (pin "1") (pinfunction "1_1") (pintype "passive"))
    )
    (net (code "201") (name "unconnected-(C3-Pad2)") (class "Default")
      (node (ref "C3") (pin "2") (pinfunction "2_2") (pintype "passive"))
    )
    (net (code "202") (name "unconnected-(C5-Pad1)") (class "Default")
      (node (ref "C5") (pin "1") (pinfunction "1_1") (pintype "passive"))
    )
    (net (code "203") (name "unconnected-(C5-Pad2)") (class "Default")
      (node (ref "C5") (pin "2") (pinfunction "2_2") (pintype "passive"))
    )
    (net (code "204") (name "unconnected-(C6-Pad1)") (class "Default")
      (node (ref "C6") (pin "1") (pinfunction "1_1") (pintype "passive"))
    )
    (net (code "205") (name "unconnected-(C6-Pad2)") (class "Default")
      (node (ref "C6") (pin "2") (pinfunction "2_2") (pintype "passive"))
    )
    (net (code "206") (name "unconnected-(C7-Pad1)") (class "Default")
      (node (ref "C7") (pin "1") (pinfunction "1_1") (pintype "passive"))
    )
    (net (code "207") (name "unconnected-(C7-Pad2)") (class "Default")
      (node (ref "C7") (pin "2") (pinfunction "2_2") (pintype "passive"))
    )
    (net (code "208") (name "unconnected-(C8-Pad2)") (class "Default")
      (node (ref "C8") (pin "2") (pinfunction "2_2") (pintype "passive"))
    )
    (net (code "209") (name "unconnected-(C9-Pad1)") (class "Default")
      (node (ref "C9") (pin "1") (pinfunction "1_1") (pintype "passive"))
    )
    (net (code "210") (name "unconnected-(C9-Pad2)") (class "Default")
      (node (ref "C9") (pin "2") (pinfunction "2_2") (pintype "passive"))
    )
    (net (code "211") (name "unconnected-(C10-Pad1)") (class "Default")
      (node (ref "C10") (pin "1") (pinfunction "1_1") (pintype "passive"))
    )
    (net (code "212") (name "unconnected-(C10-Pad2)") (class "Default")
      (node (ref "C10") (pin "2") (pinfunction "2_2") (pintype "passive"))
    )
    (net (code "213") (name "unconnected-(C11-Pad1)") (class "Default")
      (node (ref "C11") (pin "1") (pinfunction "1_1") (pintype "passive"))
    )
    (net (code "214") (name "unconnected-(C11-Pad2)") (class "Default")
      (node (ref "C11") (pin "2") (pinfunction "2_2") (pintype "passive"))
    )
    (net (code "215") (name "unconnected-(C13-Pad1)") (class "Default")
      (node (ref "C13") (pin "1") (pinfunction "1_1") (pintype "passive"))
    )
    (net (code "216") (name "unconnected-(C13-Pad2)") (class "Default")
      (node (ref "C13") (pin "2") (pinfunction "2_2") (pintype "passive"))
    )
    (net (code "217") (name "unconnected-(C14-Pad1)") (class "Default")
      (node (ref "C14") (pin "1") (pinfunction "1_1") (pintype "passive"))
    )
    (net (code "218") (name "unconnected-(C14-Pad2)") (class "Default")
      (node (ref "C14") (pin "2") (pinfunction "2_2") (pintype "passive"))
    )
    (net (code "219") (name "unconnected-(C15-Pad1)") (class "Default")
      (node (ref "C15") (pin "1") (pinfunction "1_1") (pintype "passive"))
    )
    (net (code "220") (name "unconnected-(C15-Pad2)") (class "Default")
      (node (ref "C15") (pin "2") (pinfunction "2_2") (pintype "passive"))
    )
    (net (code "221") (name "unconnected-(C16-Pad2)") (class "Default")
      (node (ref "C16") (pin "2") (pinfunction "2_2") (pintype "passive"))
    )
    (net (code "222") (name "unconnected-(C17-Pad1)") (class "Default")
      (node (ref "C17") (pin "1") (pinfunction "1_1") (pintype "passive"))
    )
    (net (code "223") (name "unconnected-(C17-Pad2)") (class "Default")
      (node (ref "C17") (pin "2") (pinfunction "2_2") (pintype "passive"))
    )
    (net (code "224") (name "unconnected-(C18-Pad1)") (class "Default")
      (node (ref "C18") (pin "1") (pinfunction "1_1") (pintype "passive"))
    )
    (net (code "225") (name "unconnected-(C18-Pad2)") (class "Default")
      (node (ref "C18") (pin "2") (pinfunction "2_2") (pintype "passive"))
    )
    (net (code "226") (name "unconnected-(C19-Pad1)") (class "Default")
      (node (ref "C19") (pin "1") (pinfunction "1_1") (pintype "passive"))
    )
    (net (code "227") (name "unconnected-(C19-Pad2)") (class "Default")
      (node (ref "C19") (pin "2") (pinfunction "2_2") (pintype "passive"))
    )
    (net (code "228") (name "unconnected-(C21-Pad1)") (class "Default")
      (node (ref "C21") (pin "1") (pinfunction "1_1") (pintype "passive"))
    )
    (net (code "229") (name "unconnected-(C21-Pad2)") (class "Default")
      (node (ref "C21") (pin "2") (pinfunction "2_2") (pintype "passive"))
    )
    (net (code "230") (name "unconnected-(C22-Pad1)") (class "Default")
      (node (ref "C22") (pin "1") (pinfunction "1_1") (pintype "passive"))
    )
    (net (code "231") (name "unconnected-(C22-Pad2)") (class "Default")
      (node (ref "C22") (pin "2") (pinfunction "2_2") (pintype "passive"))
    )
    (net (code "232") (name "unconnected-(C23-Pad1)") (class "Default")
      (node (ref "C23") (pin "1") (pinfunction "1_1") (pintype "passive"))
    )
    (net (code "233") (name "unconnected-(C23-Pad2)") (class "Default")
      (node (ref "C23") (pin "2") (pinfunction "2_2") (pintype "passive"))
    )
    (net (code "234") (name "unconnected-(CurrSensor1-C1-Pad1)") (class "Default")
      (node (ref "CurrSensor1") (pin "1") (pinfunction "C1_1") (pintype "passive"))
    )
    (net (code "235") (name "unconnected-(ORION BMS1-Pad3)") (class "Default")
      (node (ref "ORION BMS1") (pin "3") (pintype "passive"))
    )
    (net (code "236") (name "unconnected-(ORION BMS1-Pad4)") (class "Default")
      (node (ref "ORION BMS1") (pin "4") (pintype "passive"))
    )
    (net (code "237") (name "unconnected-(ORION BMS1-Pad5)") (class "Default")
      (node (ref "ORION BMS1") (pin "5") (pintype "passive"))
    )
    (net (code "238") (name "unconnected-(ORION BMS1-Pad15)") (class "Default")
      (node (ref "ORION BMS1") (pin "15") (pintype "passive"))
    )
    (net (code "239") (name "unconnected-(ORION BMS1-Therm_1-Pad9)") (class "Default")
      (node (ref "ORION BMS1") (pin "9") (pinfunction "Therm_1_9") (pintype "passive"))
    )
    (net (code "240") (name "unconnected-(ORION BMS1-Therm_2-Pad11)") (class "Default")
      (node (ref "ORION BMS1") (pin "11") (pinfunction "Therm_2_11") (pintype "passive"))
    )
    (net (code "241") (name "unconnected-(ORION BMS1-Therm_3-Pad13)") (class "Default")
      (node (ref "ORION BMS1") (pin "13") (pinfunction "Therm_3_13") (pintype "passive"))
    )
    (net (code "242") (name "unconnected-(ORION BMS1-Therm_4-Pad1)") (class "Default")
      (node (ref "ORION BMS1") (pin "1") (pinfunction "Therm_4_1") (pintype "passive"))
    )
    (net (code "243") (name "unconnected-(ORION BMS1-Therm_GND-Pad2)") (class "Default")
      (node (ref "ORION BMS1") (pin "2") (pinfunction "Therm_GND_2") (pintype "passive"))
    )
    (net (code "244") (name "unconnected-(ORION BMS1-Therm_GND-Pad10)") (class "Default")
      (node (ref "ORION BMS1") (pin "10") (pinfunction "Therm_GND_10") (pintype "passive"))
    )
    (net (code "245") (name "unconnected-(ORION BMS1-Therm_GND-Pad12)") (class "Default")
      (node (ref "ORION BMS1") (pin "12") (pinfunction "Therm_GND_12") (pintype "passive"))
    )
    (net (code "246") (name "unconnected-(ORION BMS1-Therm_GND-Pad14)") (class "Default")
      (node (ref "ORION BMS1") (pin "14") (pinfunction "Therm_GND_14") (pintype "passive"))
    )
  )
)
